# NeopixelExtension.net
KiCad netlist of a schematic drawn in EAGLE
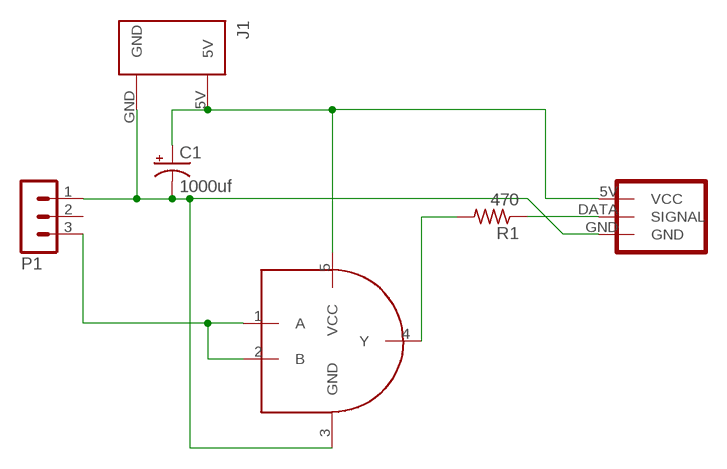
[diagram p0: schematic, sheet 1]

(export (version "E")
  (design (tool "Eeschema 10.0.6"))
  (components
    (comp (ref "C1")
      (value "1000uf")
      (footprint "eagle-import:E5-10,5")
      (libsource (lib "eagle-import") (part "CPOL-USE5-10.5"))
    )
    (comp (ref "J1")
      (value "POWER")
      (footprint "eagle-import:POWER")
      (libsource (lib "eagle-import") (part "POWER"))
    )
    (comp (ref "P1")
      (value "MA03-1")
      (footprint "eagle-import:MA03-1")
      (libsource (lib "eagle-import") (part "MA03-1"))
    )
    (comp (ref "R1")
      (value "470")
      (footprint "eagle-import:R1206")
      (libsource (lib "eagle-import") (part "R-US_R1206"))
    )
    (comp (ref "U$2")
      (value "NEOPIXEL1")
      (footprint "eagle-import:NEODIRECTSOLDERORMA03-1")
      (libsource (lib "eagle-import") (part "NEOPIXEL1"))
    )
    (comp (ref "U1")
      (value "74AHCT1G08")
      (footprint "eagle-import:SOT25")
      (libsource (lib "eagle-import") (part "74AHCT1G08"))
    )
  )
  (nets
    (net (code "1") (name "Net-(U$2-SIGNAL)") (class "Default")
      (node (ref "R1") (pin "1") (pinfunction "1_1") (pintype "passive"))
      (node (ref "U$2") (pin "DATA") (pinfunction "SIGNAL_DATA") (pintype "bidirectional"))
    )
    (net (code "2") (name "Net-(U$2-VCC)") (class "Default")
      (node (ref "C1") (pin "+") (pinfunction "+_+") (pintype "passive"))
      (node (ref "J1") (pin "5V") (pinfunction "5V_5V") (pintype "power_in"))
      (node (ref "U$2") (pin "5V") (pinfunction "VCC_5V") (pintype "power_in"))
      (node (ref "U1") (pin "5") (pinfunction "VCC_5") (pintype "bidirectional"))
    )
    (net (code "3") (name "Net-(U1-A)") (class "Default")
      (node (ref "P1") (pin "3") (pinfunction "3_3") (pintype "passive"))
      (node (ref "U1") (pin "1") (pinfunction "A_1") (pintype "bidirectional"))
      (node (ref "U1") (pin "2") (pinfunction "B_2") (pintype "bidirectional"))
    )
    (net (code "4") (name "Net-(U1-GND)") (class "Default")
      (node (ref "C1") (pin "-") (pinfunction "-_-") (pintype "passive"))
      (node (ref "J1") (pin "GND") (pinfunction "GND_GND") (pintype "power_in"))
      (node (ref "P1") (pin "1") (pinfunction "1_1") (pintype "passive"))
      (node (ref "U$2") (pin "GND") (pinfunction "GND_GND") (pintype "power_in"))
      (node (ref "U1") (pin "3") (pinfunction "GND_3") (pintype "bidirectional"))
    )
    (net (code "5") (name "Net-(U1-Y)") (class "Default")
      (node (ref "R1") (pin "2") (pinfunction "2_2") (pintype "passive"))
      (node (ref "U1") (pin "4") (pinfunction "Y_4") (pintype "bidirectional"))
    )
    (net (code "6") (name "unconnected-(P1-Pad2)") (class "Default")
      (node (ref "P1") (pin "2") (pinfunction "2_2") (pintype "passive"))
    )
  )
)
